# Othermill_Example.net
KiCad netlist of a schematic drawn in EAGLE
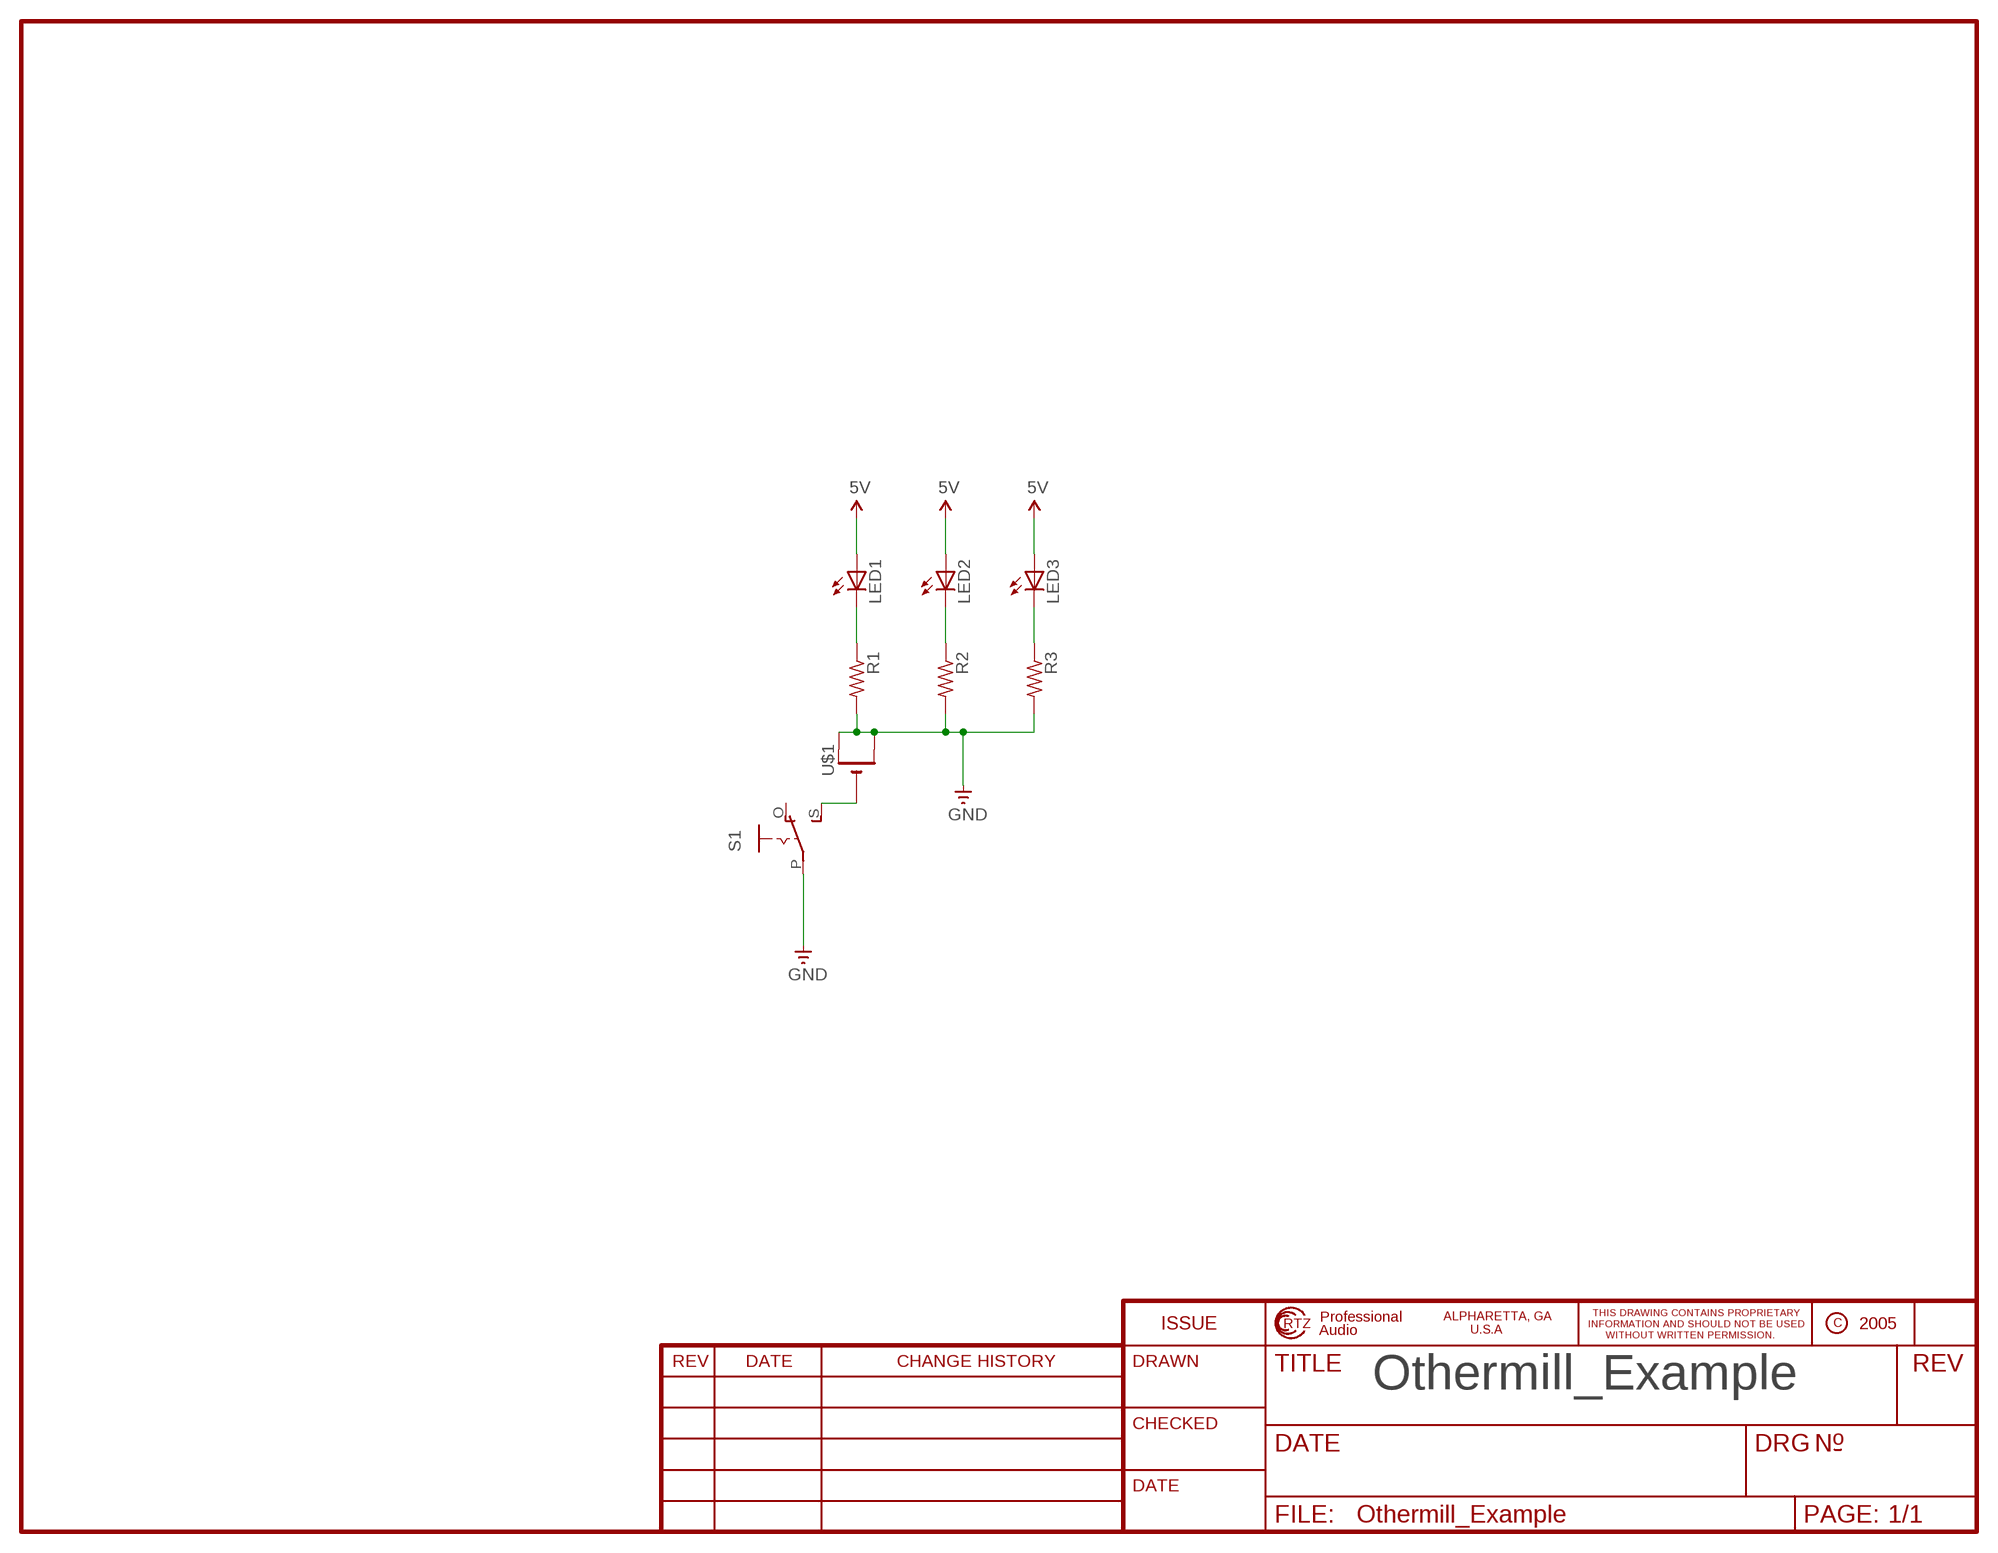
[diagram p0: schematic, sheet 1]

(export (version "E")
  (design (tool "Eeschema 10.0.6"))
  (components
    (comp (ref "LED1")
      (value "LED5MM")
      (footprint "eagle-import:LED5MM")
      (libsource (lib "eagle-import") (part "LED5MM"))
    )
    (comp (ref "LED2")
      (value "LED5MM")
      (footprint "eagle-import:LED5MM")
      (libsource (lib "eagle-import") (part "LED5MM"))
    )
    (comp (ref "LED3")
      (value "LED5MM")
      (footprint "eagle-import:LED5MM")
      (libsource (lib "eagle-import") (part "LED5MM"))
    )
    (comp (ref "R1")
      (value "R-US_0207/7")
      (footprint "eagle-import:0207_7")
      (libsource (lib "eagle-import") (part "R-US_0207/7"))
    )
    (comp (ref "R2")
      (value "R-US_0207/7")
      (footprint "eagle-import:0207_7")
      (libsource (lib "eagle-import") (part "R-US_0207/7"))
    )
    (comp (ref "R3")
      (value "R-US_0207/7")
      (footprint "eagle-import:0207_7")
      (libsource (lib "eagle-import") (part "R-US_0207/7"))
    )
    (comp (ref "S1")
      (value "EG1218S")
      (footprint "eagle-import:EG1218")
      (libsource (lib "eagle-import") (part "EG1218S"))
    )
    (comp (ref "U$1")
      (value "CR1220SMT")
      (footprint "eagle-import:CR1220-SMD")
      (libsource (lib "eagle-import") (part "CR1220SMT"))
    )
  )
  (nets
    (net (code "1") (name "5V") (class "Default")
      (node (ref "LED1") (pin "A") (pinfunction "A_A") (pintype "passive"))
      (node (ref "LED2") (pin "A") (pinfunction "A_A") (pintype "passive"))
      (node (ref "LED3") (pin "A") (pinfunction "A_A") (pintype "passive"))
    )
    (net (code "2") (name "GND") (class "Default")
      (node (ref "R1") (pin "2") (pinfunction "2_2") (pintype "passive"))
      (node (ref "R2") (pin "2") (pinfunction "2_2") (pintype "passive"))
      (node (ref "R3") (pin "2") (pinfunction "2_2") (pintype "passive"))
      (node (ref "S1") (pin "P") (pinfunction "P_P") (pintype "passive"))
      (node (ref "U$1") (pin "+$1") (pinfunction "+_+$1") (pintype "passive"))
      (node (ref "U$1") (pin "+$2") (pinfunction "+1_+$2") (pintype "passive"))
    )
    (net (code "3") (name "Net-(LED1-C)") (class "Default")
      (node (ref "LED1") (pin "K") (pinfunction "C_K") (pintype "passive"))
      (node (ref "R1") (pin "1") (pinfunction "1_1") (pintype "passive"))
    )
    (net (code "4") (name "Net-(LED2-C)") (class "Default")
      (node (ref "LED2") (pin "K") (pinfunction "C_K") (pintype "passive"))
      (node (ref "R2") (pin "1") (pinfunction "1_1") (pintype "passive"))
    )
    (net (code "5") (name "Net-(LED3-C)") (class "Default")
      (node (ref "LED3") (pin "K") (pinfunction "C_K") (pintype "passive"))
      (node (ref "R3") (pin "1") (pinfunction "1_1") (pintype "passive"))
    )
    (net (code "6") (name "Net-(S1-PadS)") (class "Default")
      (node (ref "S1") (pin "S") (pinfunction "S_S") (pintype "passive"))
      (node (ref "U$1") (pin "-") (pinfunction "-_-") (pintype "passive"))
    )
    (net (code "7") (name "unconnected-(S1-PadO)") (class "Default")
      (node (ref "S1") (pin "O") (pinfunction "O_O") (pintype "passive"))
    )
  )
)
